# SNES_Fight.net
KiCad netlist of a schematic drawn in EasyEDA
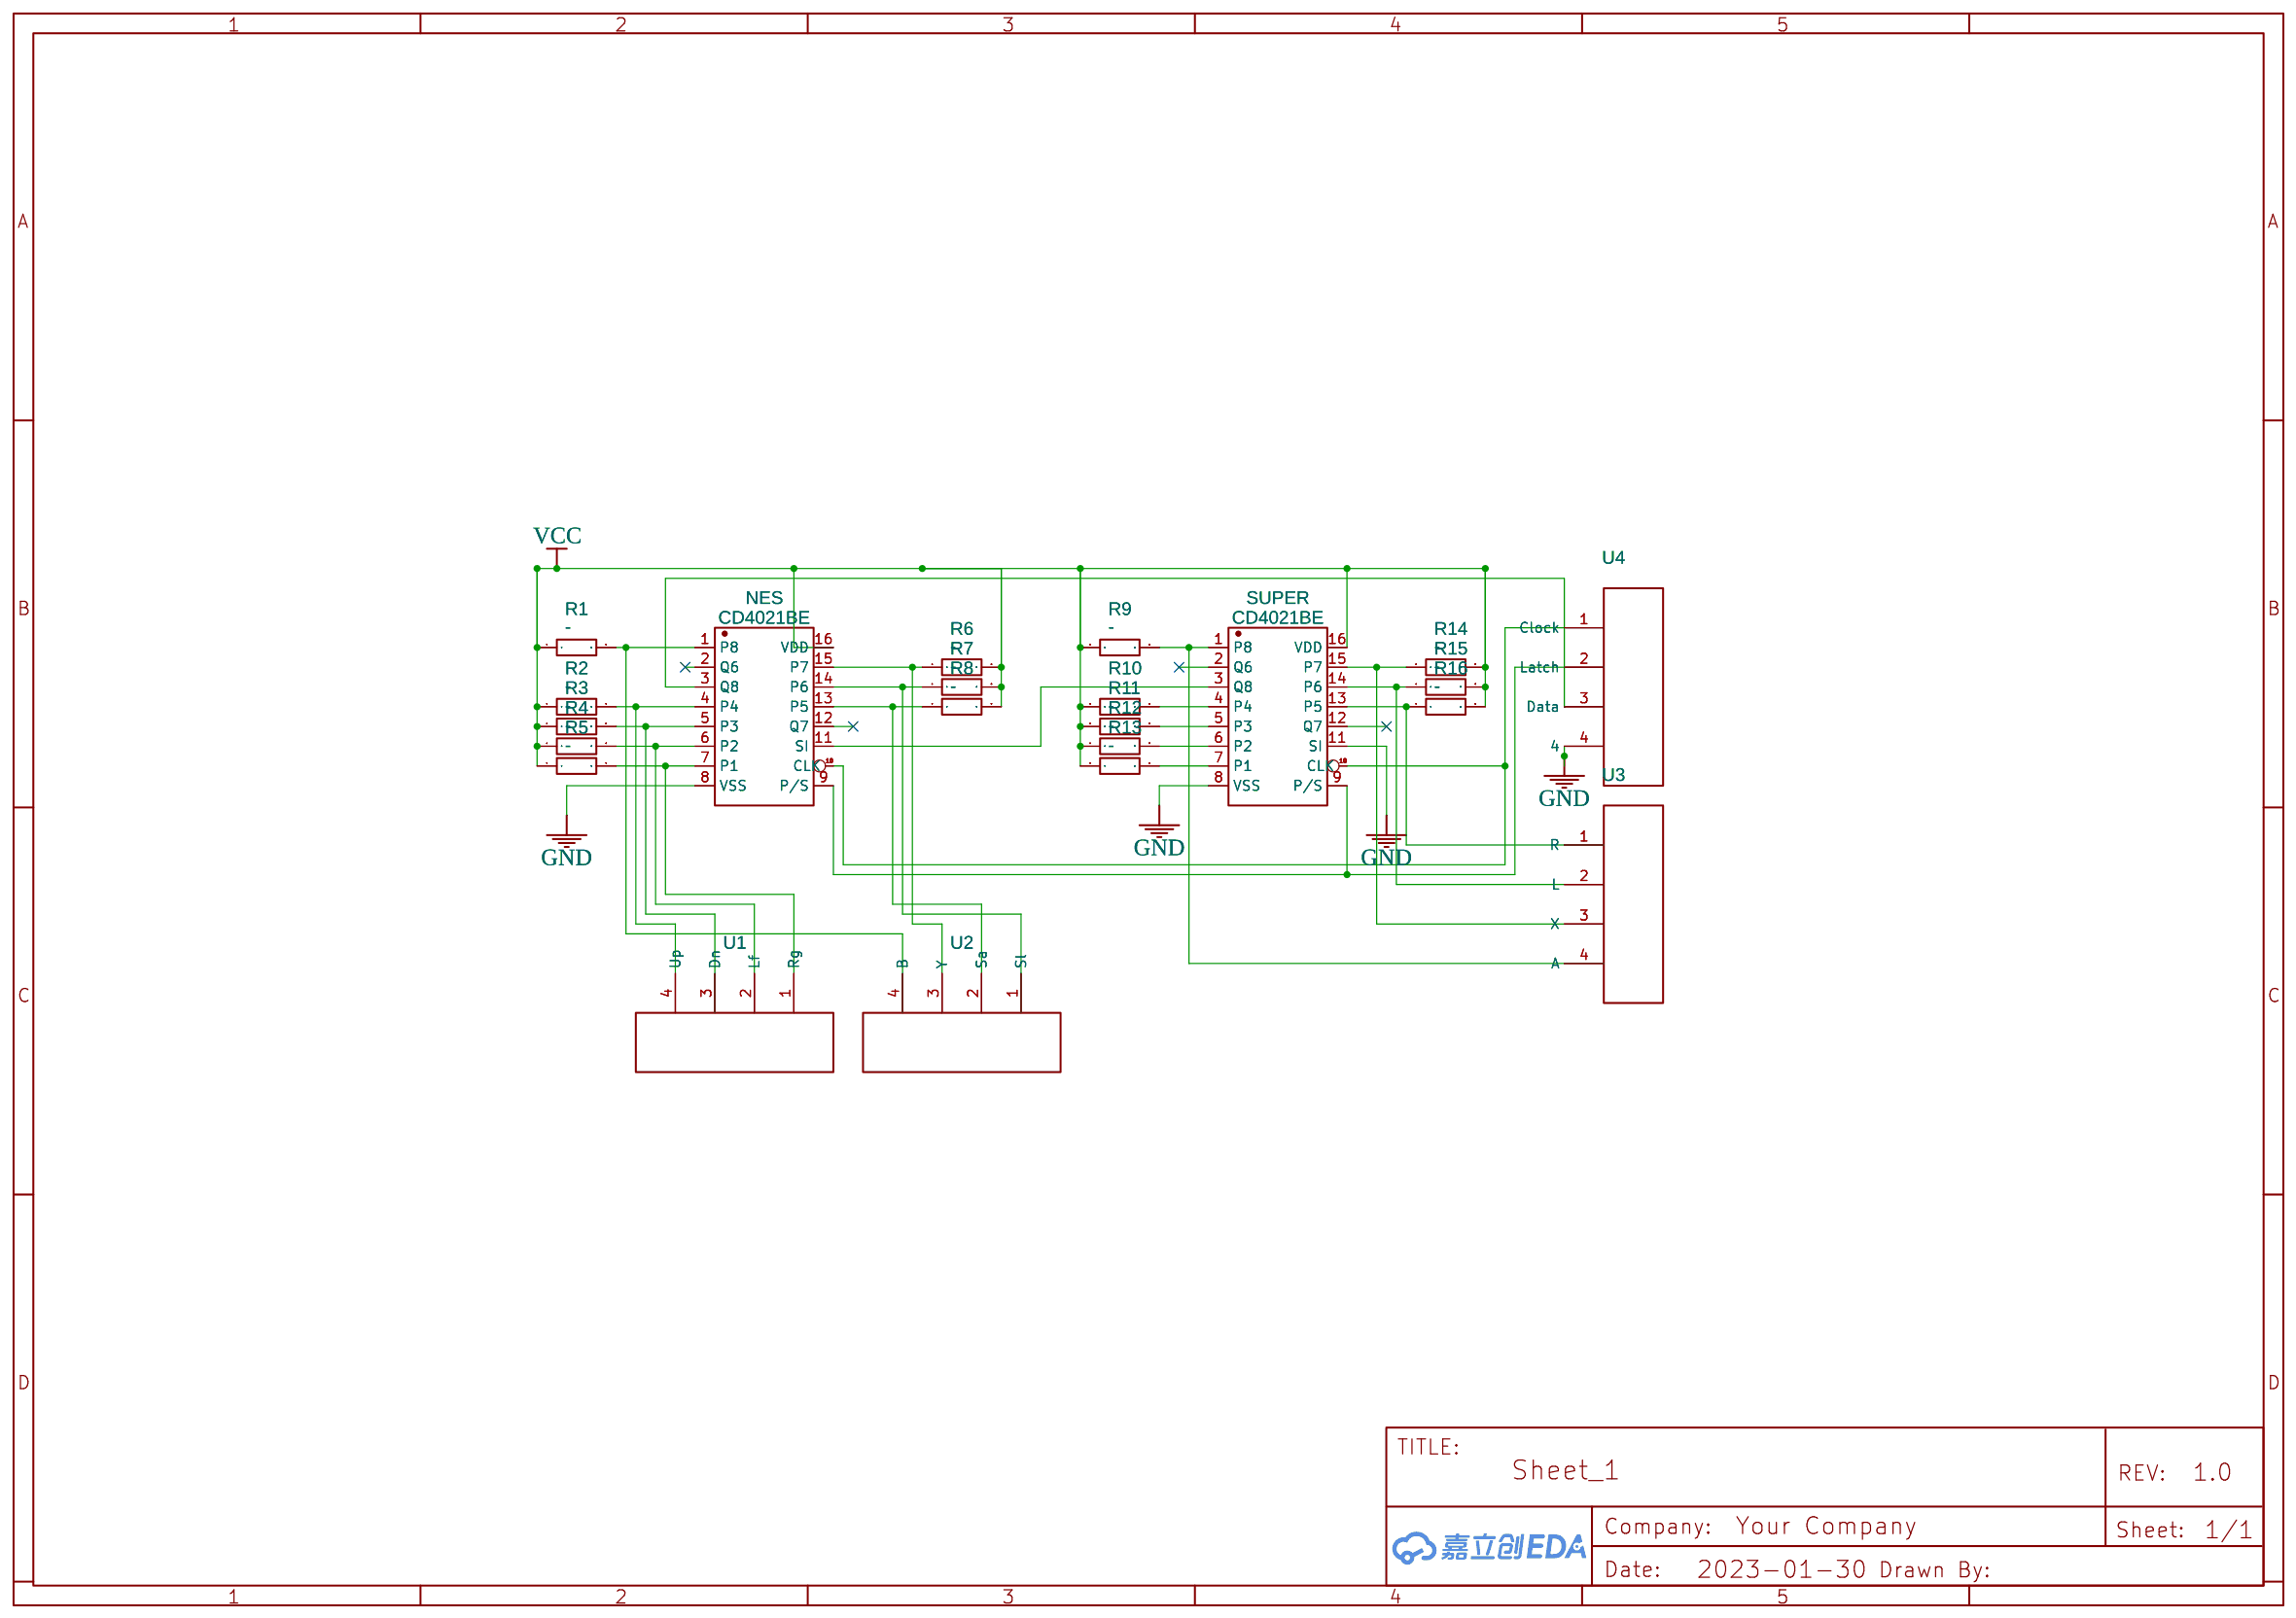
[diagram p0: schematic sheet]

(export (version "E")
  (design (tool "Eeschema 10.0.6"))
  (components
    (comp (ref "NES")
      (value "CD4021BE")
      (fields (field (name "BOM_Supplier Part") "C139390"))
      (libsource (lib "") (part "CD4021BE_1"))
    )
    (comp (ref "R1")
      (value "-")
      (fields (field (name "BOM_Manufacturer Part") "1623925-3") (field (name "BOM_Supplier Part") "C306261"))
      (libsource (lib "") (part "1623925-3"))
    )
    (comp (ref "R2")
      (value "-")
      (fields (field (name "BOM_Manufacturer Part") "1623925-3") (field (name "BOM_Supplier Part") "C306261"))
      (libsource (lib "") (part "1623925-3"))
    )
    (comp (ref "R3")
      (value "-")
      (fields (field (name "BOM_Manufacturer Part") "1623925-3") (field (name "BOM_Supplier Part") "C306261"))
      (libsource (lib "") (part "1623925-3"))
    )
    (comp (ref "R4")
      (value "-")
      (fields (field (name "BOM_Manufacturer Part") "1623925-3") (field (name "BOM_Supplier Part") "C306261"))
      (libsource (lib "") (part "1623925-3"))
    )
    (comp (ref "R5")
      (value "-")
      (fields (field (name "BOM_Manufacturer Part") "1623925-3") (field (name "BOM_Supplier Part") "C306261"))
      (libsource (lib "") (part "1623925-3"))
    )
    (comp (ref "R6")
      (value "-")
      (fields (field (name "BOM_Manufacturer Part") "1623925-3") (field (name "BOM_Supplier Part") "C306261"))
      (libsource (lib "") (part "1623925-3"))
    )
    (comp (ref "R7")
      (value "-")
      (fields (field (name "BOM_Manufacturer Part") "1623925-3") (field (name "BOM_Supplier Part") "C306261"))
      (libsource (lib "") (part "1623925-3"))
    )
    (comp (ref "R8")
      (value "-")
      (fields (field (name "BOM_Manufacturer Part") "1623925-3") (field (name "BOM_Supplier Part") "C306261"))
      (libsource (lib "") (part "1623925-3"))
    )
    (comp (ref "R9")
      (value "-")
      (fields (field (name "BOM_Manufacturer Part") "1623925-3") (field (name "BOM_Supplier Part") "C306261"))
      (libsource (lib "") (part "1623925-3"))
    )
    (comp (ref "R10")
      (value "-")
      (fields (field (name "BOM_Manufacturer Part") "1623925-3") (field (name "BOM_Supplier Part") "C306261"))
      (libsource (lib "") (part "1623925-3"))
    )
    (comp (ref "R11")
      (value "-")
      (fields (field (name "BOM_Manufacturer Part") "1623925-3") (field (name "BOM_Supplier Part") "C306261"))
      (libsource (lib "") (part "1623925-3"))
    )
    (comp (ref "R12")
      (value "-")
      (fields (field (name "BOM_Manufacturer Part") "1623925-3") (field (name "BOM_Supplier Part") "C306261"))
      (libsource (lib "") (part "1623925-3"))
    )
    (comp (ref "R13")
      (value "-")
      (fields (field (name "BOM_Manufacturer Part") "1623925-3") (field (name "BOM_Supplier Part") "C306261"))
      (libsource (lib "") (part "1623925-3"))
    )
    (comp (ref "R14")
      (value "-")
      (fields (field (name "BOM_Manufacturer Part") "1623925-3") (field (name "BOM_Supplier Part") "C306261"))
      (libsource (lib "") (part "1623925-3"))
    )
    (comp (ref "R15")
      (value "-")
      (fields (field (name "BOM_Manufacturer Part") "1623925-3") (field (name "BOM_Supplier Part") "C306261"))
      (libsource (lib "") (part "1623925-3"))
    )
    (comp (ref "R16")
      (value "-")
      (fields (field (name "BOM_Manufacturer Part") "1623925-3") (field (name "BOM_Supplier Part") "C306261"))
      (libsource (lib "") (part "1623925-3"))
    )
    (comp (ref "SUPER")
      (value "CD4021BE")
      (fields (field (name "BOM_Supplier Part") "C139390"))
      (libsource (lib "") (part "CD4021BE"))
    )
    (comp (ref "U1")
      (value "4 pin 5mm pitch terminal block")
      (fields
        (field (name "BOM_Manufacturer Part") "1935187")
        (field (name "BOM_Supplier Part") "277-1579-ND")
      )
      (libsource (lib "") (part "4 pin 5mm pitch terminal block"))
    )
    (comp (ref "U2")
      (value "4 pin 5mm pitch terminal block")
      (fields
        (field (name "BOM_Manufacturer Part") "1935187")
        (field (name "BOM_Supplier Part") "277-1579-ND")
      )
      (libsource (lib "") (part "4 pin 5mm pitch terminal block_3"))
    )
    (comp (ref "U3")
      (value "4 pin 5mm pitch terminal block")
      (fields
        (field (name "BOM_Manufacturer Part") "1935187")
        (field (name "BOM_Supplier Part") "277-1579-ND")
      )
      (libsource (lib "") (part "4 pin 5mm pitch terminal block_1"))
    )
    (comp (ref "U4")
      (value "4 pin 5mm pitch terminal block")
      (fields
        (field (name "BOM_Manufacturer Part") "1935187")
        (field (name "BOM_Supplier Part") "277-1579-ND")
      )
      (libsource (lib "") (part "4 pin 5mm pitch terminal block_2"))
    )
  )
  (nets
    (net (code "1") (name "GND") (class "Default")
      (node (ref "NES") (pin "8") (pinfunction "VSS_8") (pintype "unspecified"))
      (node (ref "SUPER") (pin "11") (pinfunction "SI_11") (pintype "unspecified"))
      (node (ref "SUPER") (pin "8") (pinfunction "VSS_8") (pintype "unspecified"))
      (node (ref "U4") (pin "4") (pinfunction "4_4") (pintype "unspecified"))
    )
    (net (code "2") (name "Net-(NES-CLK)") (class "Default")
      (node (ref "NES") (pin "10") (pinfunction "CLK_10") (pintype "unspecified"))
      (node (ref "SUPER") (pin "10") (pinfunction "CLK_10") (pintype "unspecified"))
      (node (ref "U4") (pin "1") (pinfunction "Clock_1") (pintype "unspecified"))
    )
    (net (code "3") (name "Net-(NES-P1)") (class "Default")
      (node (ref "NES") (pin "7") (pinfunction "P1_7") (pintype "unspecified"))
      (node (ref "R5") (pin "2") (pinfunction "2_2") (pintype "unspecified"))
      (node (ref "U1") (pin "1") (pinfunction "Rg_1") (pintype "unspecified"))
    )
    (net (code "4") (name "Net-(NES-P2)") (class "Default")
      (node (ref "NES") (pin "6") (pinfunction "P2_6") (pintype "unspecified"))
      (node (ref "R4") (pin "2") (pinfunction "2_2") (pintype "unspecified"))
      (node (ref "U1") (pin "2") (pinfunction "Lf_2") (pintype "unspecified"))
    )
    (net (code "5") (name "Net-(NES-P3)") (class "Default")
      (node (ref "NES") (pin "5") (pinfunction "P3_5") (pintype "unspecified"))
      (node (ref "R3") (pin "2") (pinfunction "2_2") (pintype "unspecified"))
      (node (ref "U1") (pin "3") (pinfunction "Dn_3") (pintype "unspecified"))
    )
    (net (code "6") (name "Net-(NES-P4)") (class "Default")
      (node (ref "NES") (pin "4") (pinfunction "P4_4") (pintype "unspecified"))
      (node (ref "R2") (pin "2") (pinfunction "2_2") (pintype "unspecified"))
      (node (ref "U1") (pin "4") (pinfunction "Up_4") (pintype "unspecified"))
    )
    (net (code "7") (name "Net-(NES-P5)") (class "Default")
      (node (ref "NES") (pin "13") (pinfunction "P5_13") (pintype "unspecified"))
      (node (ref "R8") (pin "1") (pinfunction "1_1") (pintype "unspecified"))
      (node (ref "U2") (pin "2") (pinfunction "Sa_2") (pintype "unspecified"))
    )
    (net (code "8") (name "Net-(NES-P6)") (class "Default")
      (node (ref "NES") (pin "14") (pinfunction "P6_14") (pintype "unspecified"))
      (node (ref "R7") (pin "1") (pinfunction "1_1") (pintype "unspecified"))
      (node (ref "U2") (pin "1") (pinfunction "Sl_1") (pintype "unspecified"))
    )
    (net (code "9") (name "Net-(NES-P7)") (class "Default")
      (node (ref "NES") (pin "15") (pinfunction "P7_15") (pintype "unspecified"))
      (node (ref "R6") (pin "1") (pinfunction "1_1") (pintype "unspecified"))
      (node (ref "U2") (pin "3") (pinfunction "Y_3") (pintype "unspecified"))
    )
    (net (code "10") (name "Net-(NES-P8)") (class "Default")
      (node (ref "NES") (pin "1") (pinfunction "P8_1") (pintype "unspecified"))
      (node (ref "R1") (pin "2") (pinfunction "2_2") (pintype "unspecified"))
      (node (ref "U2") (pin "4") (pinfunction "B_4") (pintype "unspecified"))
    )
    (net (code "11") (name "Net-(NES-P{slash}S)") (class "Default")
      (node (ref "NES") (pin "9") (pinfunction "P/S_9") (pintype "unspecified"))
      (node (ref "SUPER") (pin "9") (pinfunction "P/S_9") (pintype "unspecified"))
      (node (ref "U4") (pin "2") (pinfunction "Latch_2") (pintype "unspecified"))
    )
    (net (code "12") (name "Net-(NES-Q8)") (class "Default")
      (node (ref "NES") (pin "3") (pinfunction "Q8_3") (pintype "unspecified"))
      (node (ref "U4") (pin "3") (pinfunction "Data_3") (pintype "unspecified"))
    )
    (net (code "13") (name "Net-(NES-SI)") (class "Default")
      (node (ref "NES") (pin "11") (pinfunction "SI_11") (pintype "unspecified"))
      (node (ref "SUPER") (pin "3") (pinfunction "Q8_3") (pintype "unspecified"))
    )
    (net (code "14") (name "Net-(SUPER-P1)") (class "Default")
      (node (ref "R13") (pin "2") (pinfunction "2_2") (pintype "unspecified"))
      (node (ref "SUPER") (pin "7") (pinfunction "P1_7") (pintype "unspecified"))
    )
    (net (code "15") (name "Net-(SUPER-P2)") (class "Default")
      (node (ref "R12") (pin "2") (pinfunction "2_2") (pintype "unspecified"))
      (node (ref "SUPER") (pin "6") (pinfunction "P2_6") (pintype "unspecified"))
    )
    (net (code "16") (name "Net-(SUPER-P3)") (class "Default")
      (node (ref "R11") (pin "2") (pinfunction "2_2") (pintype "unspecified"))
      (node (ref "SUPER") (pin "5") (pinfunction "P3_5") (pintype "unspecified"))
    )
    (net (code "17") (name "Net-(SUPER-P4)") (class "Default")
      (node (ref "R10") (pin "2") (pinfunction "2_2") (pintype "unspecified"))
      (node (ref "SUPER") (pin "4") (pinfunction "P4_4") (pintype "unspecified"))
    )
    (net (code "18") (name "Net-(SUPER-P5)") (class "Default")
      (node (ref "R16") (pin "1") (pinfunction "1_1") (pintype "unspecified"))
      (node (ref "SUPER") (pin "13") (pinfunction "P5_13") (pintype "unspecified"))
      (node (ref "U3") (pin "1") (pinfunction "R_1") (pintype "unspecified"))
    )
    (net (code "19") (name "Net-(SUPER-P6)") (class "Default")
      (node (ref "R15") (pin "1") (pinfunction "1_1") (pintype "unspecified"))
      (node (ref "SUPER") (pin "14") (pinfunction "P6_14") (pintype "unspecified"))
      (node (ref "U3") (pin "2") (pinfunction "L_2") (pintype "unspecified"))
    )
    (net (code "20") (name "Net-(SUPER-P7)") (class "Default")
      (node (ref "R14") (pin "1") (pinfunction "1_1") (pintype "unspecified"))
      (node (ref "SUPER") (pin "15") (pinfunction "P7_15") (pintype "unspecified"))
      (node (ref "U3") (pin "3") (pinfunction "X_3") (pintype "unspecified"))
    )
    (net (code "21") (name "Net-(SUPER-P8)") (class "Default")
      (node (ref "R9") (pin "2") (pinfunction "2_2") (pintype "unspecified"))
      (node (ref "SUPER") (pin "1") (pinfunction "P8_1") (pintype "unspecified"))
      (node (ref "U3") (pin "4") (pinfunction "A_4") (pintype "unspecified"))
    )
    (net (code "22") (name "VCC") (class "Default")
      (node (ref "NES") (pin "16") (pinfunction "VDD_16") (pintype "unspecified"))
      (node (ref "R1") (pin "1") (pinfunction "1_1") (pintype "unspecified"))
      (node (ref "R10") (pin "1") (pinfunction "1_1") (pintype "unspecified"))
      (node (ref "R11") (pin "1") (pinfunction "1_1") (pintype "unspecified"))
      (node (ref "R12") (pin "1") (pinfunction "1_1") (pintype "unspecified"))
      (node (ref "R13") (pin "1") (pinfunction "1_1") (pintype "unspecified"))
      (node (ref "R14") (pin "2") (pinfunction "2_2") (pintype "unspecified"))
      (node (ref "R15") (pin "2") (pinfunction "2_2") (pintype "unspecified"))
      (node (ref "R16") (pin "2") (pinfunction "2_2") (pintype "unspecified"))
      (node (ref "R2") (pin "1") (pinfunction "1_1") (pintype "unspecified"))
      (node (ref "R3") (pin "1") (pinfunction "1_1") (pintype "unspecified"))
      (node (ref "R4") (pin "1") (pinfunction "1_1") (pintype "unspecified"))
      (node (ref "R5") (pin "1") (pinfunction "1_1") (pintype "unspecified"))
      (node (ref "R6") (pin "2") (pinfunction "2_2") (pintype "unspecified"))
      (node (ref "R7") (pin "2") (pinfunction "2_2") (pintype "unspecified"))
      (node (ref "R8") (pin "2") (pinfunction "2_2") (pintype "unspecified"))
      (node (ref "R9") (pin "1") (pinfunction "1_1") (pintype "unspecified"))
      (node (ref "SUPER") (pin "16") (pinfunction "VDD_16") (pintype "unspecified"))
    )
    (net (code "23") (name "unconnected-(NES-Q6-Pad2)") (class "Default")
      (node (ref "NES") (pin "2") (pinfunction "Q6_2") (pintype "unspecified+no_connect"))
    )
    (net (code "24") (name "unconnected-(NES-Q7-Pad12)") (class "Default")
      (node (ref "NES") (pin "12") (pinfunction "Q7_12") (pintype "unspecified+no_connect"))
    )
    (net (code "25") (name "unconnected-(SUPER-Q6-Pad2)") (class "Default")
      (node (ref "SUPER") (pin "2") (pinfunction "Q6_2") (pintype "unspecified+no_connect"))
    )
    (net (code "26") (name "unconnected-(SUPER-Q7-Pad12)") (class "Default")
      (node (ref "SUPER") (pin "12") (pinfunction "Q7_12") (pintype "unspecified+no_connect"))
    )
  )
)
